# Motor.net
KiCad netlist of a schematic drawn in Altium Designer
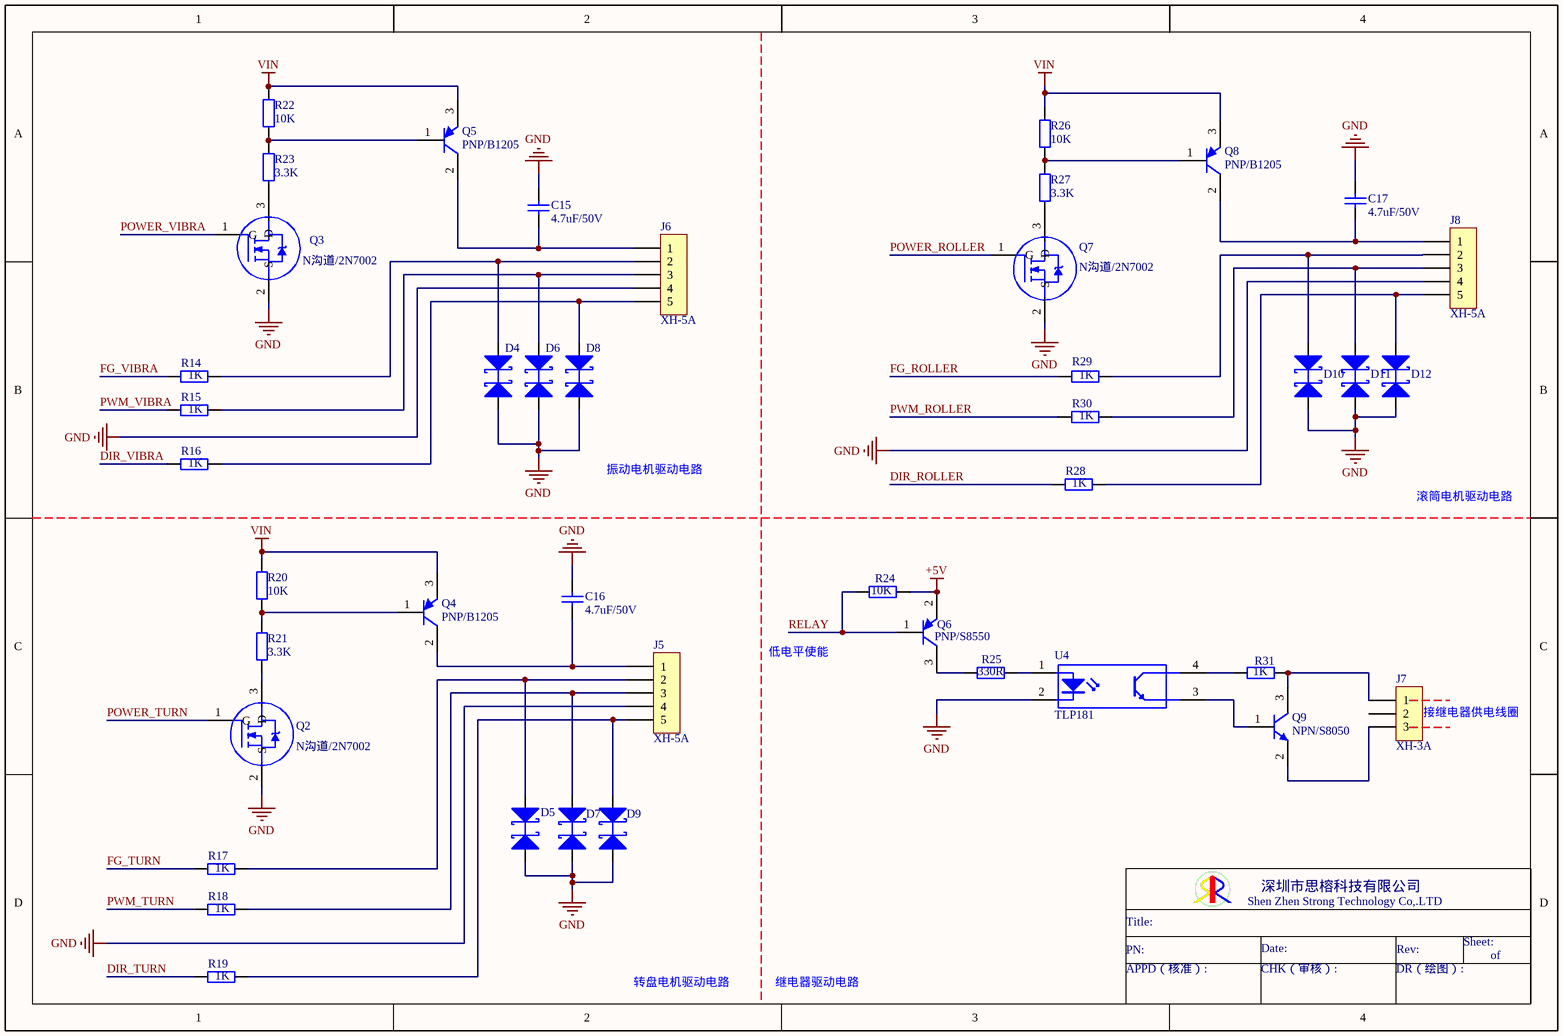
[diagram p0: Motor.SchDoc]

(export (version "E")
  (design (tool "Eeschema 10.0.6"))
  (components
    (comp (ref "C15")
      (value "4.7uF/50V")
      (footprint "0603C")
      (description "瓷片电容,4.7uF,5%,X7R,50V,0603")
      (libsource (lib "SR SCH Library V02") (part "C4.7uF-0603"))
    )
    (comp (ref "C16")
      (value "4.7uF/50V")
      (footprint "0603C")
      (description "瓷片电容,4.7uF,5%,X7R,50V,0603")
      (libsource (lib "SR SCH Library V02") (part "C4.7uF-0603"))
    )
    (comp (ref "C17")
      (value "4.7uF/50V")
      (footprint "0603C")
      (description "瓷片电容,4.7uF,5%,X7R,50V,0603")
      (libsource (lib "SR SCH Library V02") (part "C4.7uF-0603"))
    )
    (comp (ref "D4")
      (value "ESD5B5.0ST1G")
      (footprint "SOD-523")
      (description "TVS管,5V,SOD-523")
      (libsource (lib "SR SCH Library V02") (part "ESD5B5.0ST1G"))
    )
    (comp (ref "D5")
      (value "ESD5B5.0ST1G")
      (footprint "SOD-523")
      (description "TVS管,5V,SOD-523")
      (libsource (lib "SR SCH Library V02") (part "ESD5B5.0ST1G"))
    )
    (comp (ref "D6")
      (value "ESD5B5.0ST1G")
      (footprint "SOD-523")
      (description "TVS管,5V,SOD-523")
      (libsource (lib "SR SCH Library V02") (part "ESD5B5.0ST1G"))
    )
    (comp (ref "D7")
      (value "ESD5B5.0ST1G")
      (footprint "SOD-523")
      (description "TVS管,5V,SOD-523")
      (libsource (lib "SR SCH Library V02") (part "ESD5B5.0ST1G"))
    )
    (comp (ref "D8")
      (value "ESD5B5.0ST1G")
      (footprint "SOD-523")
      (description "TVS管,5V,SOD-523")
      (libsource (lib "SR SCH Library V02") (part "ESD5B5.0ST1G"))
    )
    (comp (ref "D9")
      (value "ESD5B5.0ST1G")
      (footprint "SOD-523")
      (description "TVS管,5V,SOD-523")
      (libsource (lib "SR SCH Library V02") (part "ESD5B5.0ST1G"))
    )
    (comp (ref "D10")
      (value "ESD5B5.0ST1G")
      (footprint "SOD-523")
      (description "TVS管,5V,SOD-523")
      (libsource (lib "SR SCH Library V02") (part "ESD5B5.0ST1G"))
    )
    (comp (ref "D11")
      (value "ESD5B5.0ST1G")
      (footprint "SOD-523")
      (description "TVS管,5V,SOD-523")
      (libsource (lib "SR SCH Library V02") (part "ESD5B5.0ST1G"))
    )
    (comp (ref "D12")
      (value "ESD5B5.0ST1G")
      (footprint "SOD-523")
      (description "TVS管,5V,SOD-523")
      (libsource (lib "SR SCH Library V02") (part "ESD5B5.0ST1G"))
    )
    (comp (ref "J5")
      (value "XH-5A")
      (footprint "CN5-2.54")
      (description "CONN,XH-5A,5PIN,2.54mm插座")
      (libsource (lib "SR SCH Library V02") (part "CONN-XH-5A"))
    )
    (comp (ref "J6")
      (value "XH-5A")
      (footprint "CN5-2.54")
      (description "CONN,XH-5A,5PIN,2.54mm插座")
      (libsource (lib "SR SCH Library V02") (part "CONN-XH-5A"))
    )
    (comp (ref "J7")
      (value "XH-3A")
      (footprint "CN3-2.54")
      (description "CONN,XH-3A,3PIN,2.54mm插座")
      (libsource (lib "SR SCH Library V02") (part "CONN-XH-3A"))
    )
    (comp (ref "J8")
      (value "XH-5A")
      (footprint "CN5-2.54")
      (description "CONN,XH-5A,5PIN,2.54mm插座")
      (libsource (lib "SR SCH Library V02") (part "CONN-XH-5A"))
    )
    (comp (ref "Q2")
      (value "N沟道/2N7002")
      (footprint "SOT-23")
      (description "N沟道场效应管，2N7002，SOT-23")
      (libsource (lib "SR SCH Library V02") (part "2N7002"))
    )
    (comp (ref "Q3")
      (value "N沟道/2N7002")
      (footprint "SOT-23")
      (description "N沟道场效应管，2N7002，SOT-23")
      (libsource (lib "SR SCH Library V02") (part "2N7002"))
    )
    (comp (ref "Q4")
      (value "PNP/B1205")
      (footprint "TO-252")
      (description "PNP型三极管，B1205，SOT－23")
      (libsource (lib "Next_SCHlib") (part "B1205"))
    )
    (comp (ref "Q5")
      (value "PNP/B1205")
      (footprint "TO-252")
      (description "PNP型三极管，B1205，SOT－23")
      (libsource (lib "Next_SCHlib") (part "B1205"))
    )
    (comp (ref "Q6")
      (value "PNP/S8550")
      (footprint "SOT-23")
      (description "PNP型三极管，S8550，SOT－23")
      (libsource (lib "SR SCH Library V02") (part "S8550"))
    )
    (comp (ref "Q7")
      (value "N沟道/2N7002")
      (footprint "SOT-23")
      (description "N沟道场效应管，2N7002，SOT-23")
      (libsource (lib "SR SCH Library V02") (part "2N7002"))
    )
    (comp (ref "Q8")
      (value "PNP/B1205")
      (footprint "TO-252")
      (description "PNP型三极管，B1205，SOT－23")
      (libsource (lib "Next_SCHlib") (part "B1205"))
    )
    (comp (ref "Q9")
      (value "NPN/S8050")
      (footprint "TO-92MOD")
      (description "NPN型三极管，S8050，SOT－23")
      (libsource (lib "SR SCH Library V02") (part "S8050"))
    )
    (comp (ref "R14")
      (value "1K")
      (footprint "0603R")
      (description "金属膜电阻,1K,1%,1/10W,0603")
      (libsource (lib "SR SCH Library V02") (part "R1K-0603"))
    )
    (comp (ref "R15")
      (value "1K")
      (footprint "0603R")
      (description "金属膜电阻,1K,1%,1/10W,0603")
      (libsource (lib "SR SCH Library V02") (part "R1K-0603"))
    )
    (comp (ref "R16")
      (value "1K")
      (footprint "0603R")
      (description "金属膜电阻,1K,1%,1/10W,0603")
      (libsource (lib "SR SCH Library V02") (part "R1K-0603"))
    )
    (comp (ref "R17")
      (value "1K")
      (footprint "0603R")
      (description "金属膜电阻,1K,1%,1/10W,0603")
      (libsource (lib "SR SCH Library V02") (part "R1K-0603"))
    )
    (comp (ref "R18")
      (value "1K")
      (footprint "0603R")
      (description "金属膜电阻,1K,1%,1/10W,0603")
      (libsource (lib "SR SCH Library V02") (part "R1K-0603"))
    )
    (comp (ref "R19")
      (value "1K")
      (footprint "0603R")
      (description "金属膜电阻,1K,1%,1/10W,0603")
      (libsource (lib "SR SCH Library V02") (part "R1K-0603"))
    )
    (comp (ref "R20")
      (value "10K")
      (footprint "0603R")
      (description "金属膜电阻,10K,1%,1/10W,0603")
      (libsource (lib "SR SCH Library V02") (part "R10K-0603"))
    )
    (comp (ref "R21")
      (value "3.3K")
      (footprint "0805R")
      (description "金属膜电阻,3.3K,1%,1/10W,0603")
      (libsource (lib "SR SCH Library V02") (part "R3.3K-0603"))
    )
    (comp (ref "R22")
      (value "10K")
      (footprint "0603R")
      (description "金属膜电阻,10K,1%,1/10W,0603")
      (libsource (lib "") (part "R10K-0603_2"))
    )
    (comp (ref "R23")
      (value "3.3K")
      (footprint "0805R")
      (description "金属膜电阻,3.3K,1%,1/10W,0603")
      (libsource (lib "SR SCH Library V02") (part "R3.3K-0603"))
    )
    (comp (ref "R24")
      (value "10K")
      (footprint "0603R")
      (description "金属膜电阻,10K,1%,1/10W,0603")
      (libsource (lib "") (part "R10K-0603_1"))
    )
    (comp (ref "R25")
      (value "330R")
      (footprint "0603R")
      (description "金属膜电阻,330R,1%,1/10W,0603")
      (libsource (lib "SR SCH Library V02") (part "R33R-0805"))
    )
    (comp (ref "R26")
      (value "10K")
      (footprint "0603R")
      (description "金属膜电阻,10K,1%,1/10W,0603")
      (libsource (lib "SR SCH Library V02") (part "R10K-0603"))
    )
    (comp (ref "R27")
      (value "3.3K")
      (footprint "0805R")
      (description "金属膜电阻,3.3K,1%,1/10W,0603")
      (libsource (lib "SR SCH Library V02") (part "R3.3K-0603"))
    )
    (comp (ref "R28")
      (value "1K")
      (footprint "0603R")
      (description "金属膜电阻,1K,1%,1/10W,0603")
      (libsource (lib "SR SCH Library V02") (part "R1K-0603"))
    )
    (comp (ref "R29")
      (value "1K")
      (footprint "0603R")
      (description "金属膜电阻,1K,1%,1/10W,0603")
      (libsource (lib "SR SCH Library V02") (part "R1K-0603"))
    )
    (comp (ref "R30")
      (value "1K")
      (footprint "0603R")
      (description "金属膜电阻,1K,1%,1/10W,0603")
      (libsource (lib "SR SCH Library V02") (part "R1K-0603"))
    )
    (comp (ref "R31")
      (value "1K")
      (footprint "0603R")
      (description "金属膜电阻,1K,1%,1/10W,0603")
      (libsource (lib "SR SCH Library V02") (part "R1K-0603"))
    )
    (comp (ref "U4")
      (value "TLP181")
      (footprint "SOP4-2.54")
      (description "光耦，TLP181，SOP4")
      (libsource (lib "SR SCH Library V02") (part "TLP181"))
    )
  )
  (nets
    (net (code "1") (name "+5V") (class "Default")
      (node (ref "Q6") (pin "2") (pinfunction "E_2") (pintype "passive"))
      (node (ref "R24") (pin "1") (pinfunction "1_1") (pintype "passive"))
    )
    (net (code "2") (name "/DIR_ROLLER") (class "Default")
      (node (ref "R28") (pin "1") (pinfunction "1_1") (pintype "passive"))
    )
    (net (code "3") (name "/DIR_TURN") (class "Default")
      (node (ref "R19") (pin "1") (pinfunction "1_1") (pintype "passive"))
    )
    (net (code "4") (name "/DIR_VIBRA") (class "Default")
      (node (ref "R16") (pin "1") (pinfunction "1_1") (pintype "passive"))
    )
    (net (code "5") (name "/FG_ROLLER") (class "Default")
      (node (ref "R29") (pin "1") (pinfunction "1_1") (pintype "passive"))
    )
    (net (code "6") (name "/FG_TURN") (class "Default")
      (node (ref "R17") (pin "1") (pinfunction "1_1") (pintype "passive"))
    )
    (net (code "7") (name "/FG_VIBRA") (class "Default")
      (node (ref "R14") (pin "1") (pinfunction "1_1") (pintype "passive"))
    )
    (net (code "8") (name "/POWER_ROLLER") (class "Default")
      (node (ref "Q7") (pin "1") (pinfunction "G_1") (pintype "passive"))
    )
    (net (code "9") (name "/POWER_TURN") (class "Default")
      (node (ref "Q2") (pin "1") (pinfunction "G_1") (pintype "passive"))
    )
    (net (code "10") (name "/POWER_VIBRA") (class "Default")
      (node (ref "Q3") (pin "1") (pinfunction "G_1") (pintype "passive"))
    )
    (net (code "11") (name "/PWM_ROLLER") (class "Default")
      (node (ref "R30") (pin "1") (pinfunction "1_1") (pintype "passive"))
    )
    (net (code "12") (name "/PWM_TURN") (class "Default")
      (node (ref "R18") (pin "1") (pinfunction "1_1") (pintype "passive"))
    )
    (net (code "13") (name "/PWM_VIBRA") (class "Default")
      (node (ref "R15") (pin "1") (pinfunction "1_1") (pintype "passive"))
    )
    (net (code "14") (name "/RELAY") (class "Default")
      (node (ref "Q6") (pin "1") (pinfunction "B_1") (pintype "passive"))
      (node (ref "R24") (pin "2") (pinfunction "2_2") (pintype "passive"))
    )
    (net (code "15") (name "GND") (class "Default")
      (node (ref "C15") (pin "2") (pinfunction "2_2") (pintype "passive"))
      (node (ref "C16") (pin "2") (pinfunction "2_2") (pintype "passive"))
      (node (ref "C17") (pin "2") (pinfunction "2_2") (pintype "passive"))
      (node (ref "D10") (pin "2") (pinfunction "2_2") (pintype "passive"))
      (node (ref "D11") (pin "2") (pinfunction "2_2") (pintype "passive"))
      (node (ref "D12") (pin "2") (pinfunction "2_2") (pintype "passive"))
      (node (ref "D4") (pin "2") (pinfunction "2_2") (pintype "passive"))
      (node (ref "D5") (pin "2") (pinfunction "2_2") (pintype "passive"))
      (node (ref "D6") (pin "2") (pinfunction "2_2") (pintype "passive"))
      (node (ref "D7") (pin "2") (pinfunction "2_2") (pintype "passive"))
      (node (ref "D8") (pin "2") (pinfunction "2_2") (pintype "passive"))
      (node (ref "D9") (pin "2") (pinfunction "2_2") (pintype "passive"))
      (node (ref "J5") (pin "4") (pinfunction "4_4") (pintype "passive"))
      (node (ref "J6") (pin "4") (pinfunction "4_4") (pintype "passive"))
      (node (ref "J8") (pin "4") (pinfunction "4_4") (pintype "passive"))
      (node (ref "Q2") (pin "2") (pinfunction "S_2") (pintype "passive"))
      (node (ref "Q3") (pin "2") (pinfunction "S_2") (pintype "passive"))
      (node (ref "Q7") (pin "2") (pinfunction "S_2") (pintype "passive"))
      (node (ref "U4") (pin "2") (pinfunction "K_2") (pintype "passive"))
    )
    (net (code "16") (name "Net-(D4-Pad1)") (class "Default")
      (node (ref "D4") (pin "1") (pinfunction "1_1") (pintype "passive"))
      (node (ref "J6") (pin "2") (pinfunction "2_2") (pintype "passive"))
      (node (ref "R14") (pin "2") (pinfunction "2_2") (pintype "passive"))
    )
    (net (code "17") (name "Net-(D5-Pad1)") (class "Default")
      (node (ref "D5") (pin "1") (pinfunction "1_1") (pintype "passive"))
      (node (ref "J5") (pin "2") (pinfunction "2_2") (pintype "passive"))
      (node (ref "R17") (pin "2") (pinfunction "2_2") (pintype "passive"))
    )
    (net (code "18") (name "Net-(D6-Pad1)") (class "Default")
      (node (ref "D6") (pin "1") (pinfunction "1_1") (pintype "passive"))
      (node (ref "J6") (pin "3") (pinfunction "3_3") (pintype "passive"))
      (node (ref "R15") (pin "2") (pinfunction "2_2") (pintype "passive"))
    )
    (net (code "19") (name "Net-(D7-Pad1)") (class "Default")
      (node (ref "D7") (pin "1") (pinfunction "1_1") (pintype "passive"))
      (node (ref "J5") (pin "3") (pinfunction "3_3") (pintype "passive"))
      (node (ref "R18") (pin "2") (pinfunction "2_2") (pintype "passive"))
    )
    (net (code "20") (name "Net-(D8-Pad1)") (class "Default")
      (node (ref "D8") (pin "1") (pinfunction "1_1") (pintype "passive"))
      (node (ref "J6") (pin "5") (pinfunction "5_5") (pintype "passive"))
      (node (ref "R16") (pin "2") (pinfunction "2_2") (pintype "passive"))
    )
    (net (code "21") (name "Net-(D9-Pad1)") (class "Default")
      (node (ref "D9") (pin "1") (pinfunction "1_1") (pintype "passive"))
      (node (ref "J5") (pin "5") (pinfunction "5_5") (pintype "passive"))
      (node (ref "R19") (pin "2") (pinfunction "2_2") (pintype "passive"))
    )
    (net (code "22") (name "Net-(D10-Pad1)") (class "Default")
      (node (ref "D10") (pin "1") (pinfunction "1_1") (pintype "passive"))
      (node (ref "J8") (pin "2") (pinfunction "2_2") (pintype "passive"))
      (node (ref "R29") (pin "2") (pinfunction "2_2") (pintype "passive"))
    )
    (net (code "23") (name "Net-(D11-Pad1)") (class "Default")
      (node (ref "D11") (pin "1") (pinfunction "1_1") (pintype "passive"))
      (node (ref "J8") (pin "3") (pinfunction "3_3") (pintype "passive"))
      (node (ref "R30") (pin "2") (pinfunction "2_2") (pintype "passive"))
    )
    (net (code "24") (name "Net-(D12-Pad1)") (class "Default")
      (node (ref "D12") (pin "1") (pinfunction "1_1") (pintype "passive"))
      (node (ref "J8") (pin "5") (pinfunction "5_5") (pintype "passive"))
      (node (ref "R28") (pin "2") (pinfunction "2_2") (pintype "passive"))
    )
    (net (code "25") (name "Net-(Q2-D)") (class "Default")
      (node (ref "Q2") (pin "3") (pinfunction "D_3") (pintype "passive"))
      (node (ref "R21") (pin "1") (pinfunction "1_1") (pintype "passive"))
    )
    (net (code "26") (name "Net-(Q3-D)") (class "Default")
      (node (ref "Q3") (pin "3") (pinfunction "D_3") (pintype "passive"))
      (node (ref "R23") (pin "1") (pinfunction "1_1") (pintype "passive"))
    )
    (net (code "27") (name "Net-(Q4-B)") (class "Default")
      (node (ref "Q4") (pin "1") (pinfunction "B_1") (pintype "passive"))
      (node (ref "R20") (pin "2") (pinfunction "2_2") (pintype "passive"))
      (node (ref "R21") (pin "2") (pinfunction "2_2") (pintype "passive"))
    )
    (net (code "28") (name "Net-(Q4-C)") (class "Default")
      (node (ref "C16") (pin "1") (pinfunction "1_1") (pintype "passive"))
      (node (ref "J5") (pin "1") (pinfunction "1_1") (pintype "passive"))
      (node (ref "Q4") (pin "2") (pinfunction "C_2") (pintype "passive"))
    )
    (net (code "29") (name "Net-(Q5-B)") (class "Default")
      (node (ref "Q5") (pin "1") (pinfunction "B_1") (pintype "passive"))
      (node (ref "R22") (pin "1") (pinfunction "1_1") (pintype "passive"))
      (node (ref "R23") (pin "2") (pinfunction "2_2") (pintype "passive"))
    )
    (net (code "30") (name "Net-(Q5-C)") (class "Default")
      (node (ref "C15") (pin "1") (pinfunction "1_1") (pintype "passive"))
      (node (ref "J6") (pin "1") (pinfunction "1_1") (pintype "passive"))
      (node (ref "Q5") (pin "2") (pinfunction "C_2") (pintype "passive"))
    )
    (net (code "31") (name "Net-(Q6-C)") (class "Default")
      (node (ref "Q6") (pin "3") (pinfunction "C_3") (pintype "passive"))
      (node (ref "R25") (pin "1") (pinfunction "1_1") (pintype "passive"))
    )
    (net (code "32") (name "Net-(Q7-D)") (class "Default")
      (node (ref "Q7") (pin "3") (pinfunction "D_3") (pintype "passive"))
      (node (ref "R27") (pin "1") (pinfunction "1_1") (pintype "passive"))
    )
    (net (code "33") (name "Net-(Q8-B)") (class "Default")
      (node (ref "Q8") (pin "1") (pinfunction "B_1") (pintype "passive"))
      (node (ref "R26") (pin "2") (pinfunction "2_2") (pintype "passive"))
      (node (ref "R27") (pin "2") (pinfunction "2_2") (pintype "passive"))
    )
    (net (code "34") (name "Net-(Q8-C)") (class "Default")
      (node (ref "C17") (pin "1") (pinfunction "1_1") (pintype "passive"))
      (node (ref "J8") (pin "1") (pinfunction "1_1") (pintype "passive"))
      (node (ref "Q8") (pin "2") (pinfunction "C_2") (pintype "passive"))
    )
    (net (code "35") (name "Net-(Q9-B)") (class "Default")
      (node (ref "Q9") (pin "1") (pinfunction "B_1") (pintype "passive"))
      (node (ref "U4") (pin "3") (pinfunction "E_3") (pintype "passive"))
    )
    (net (code "36") (name "Net-(Q9-C)") (class "Default")
      (node (ref "J7") (pin "1") (pinfunction "1_1") (pintype "passive"))
      (node (ref "Q9") (pin "3") (pinfunction "C_3") (pintype "passive"))
      (node (ref "R31") (pin "2") (pinfunction "2_2") (pintype "passive"))
    )
    (net (code "37") (name "Net-(Q9-E)") (class "Default")
      (node (ref "J7") (pin "3") (pinfunction "3_3") (pintype "passive"))
      (node (ref "Q9") (pin "2") (pinfunction "E_2") (pintype "passive"))
    )
    (net (code "38") (name "Net-(U4-A)") (class "Default")
      (node (ref "R25") (pin "2") (pinfunction "2_2") (pintype "passive"))
      (node (ref "U4") (pin "1") (pinfunction "A_1") (pintype "passive"))
    )
    (net (code "39") (name "Net-(U4-C)") (class "Default")
      (node (ref "R31") (pin "1") (pinfunction "1_1") (pintype "passive"))
      (node (ref "U4") (pin "4") (pinfunction "C_4") (pintype "passive"))
    )
    (net (code "40") (name "VIN") (class "Default")
      (node (ref "Q4") (pin "3") (pinfunction "E_3") (pintype "passive"))
      (node (ref "Q5") (pin "3") (pinfunction "E_3") (pintype "passive"))
      (node (ref "Q8") (pin "3") (pinfunction "E_3") (pintype "passive"))
      (node (ref "R20") (pin "1") (pinfunction "1_1") (pintype "passive"))
      (node (ref "R22") (pin "2") (pinfunction "2_2") (pintype "passive"))
      (node (ref "R26") (pin "1") (pinfunction "1_1") (pintype "passive"))
    )
    (net (code "41") (name "unconnected-(J7-Pad2)") (class "Default")
      (node (ref "J7") (pin "2") (pinfunction "2_2") (pintype "passive"))
    )
  )
)
